# Power_Board.net
KiCad netlist of a schematic drawn in Altium Designer
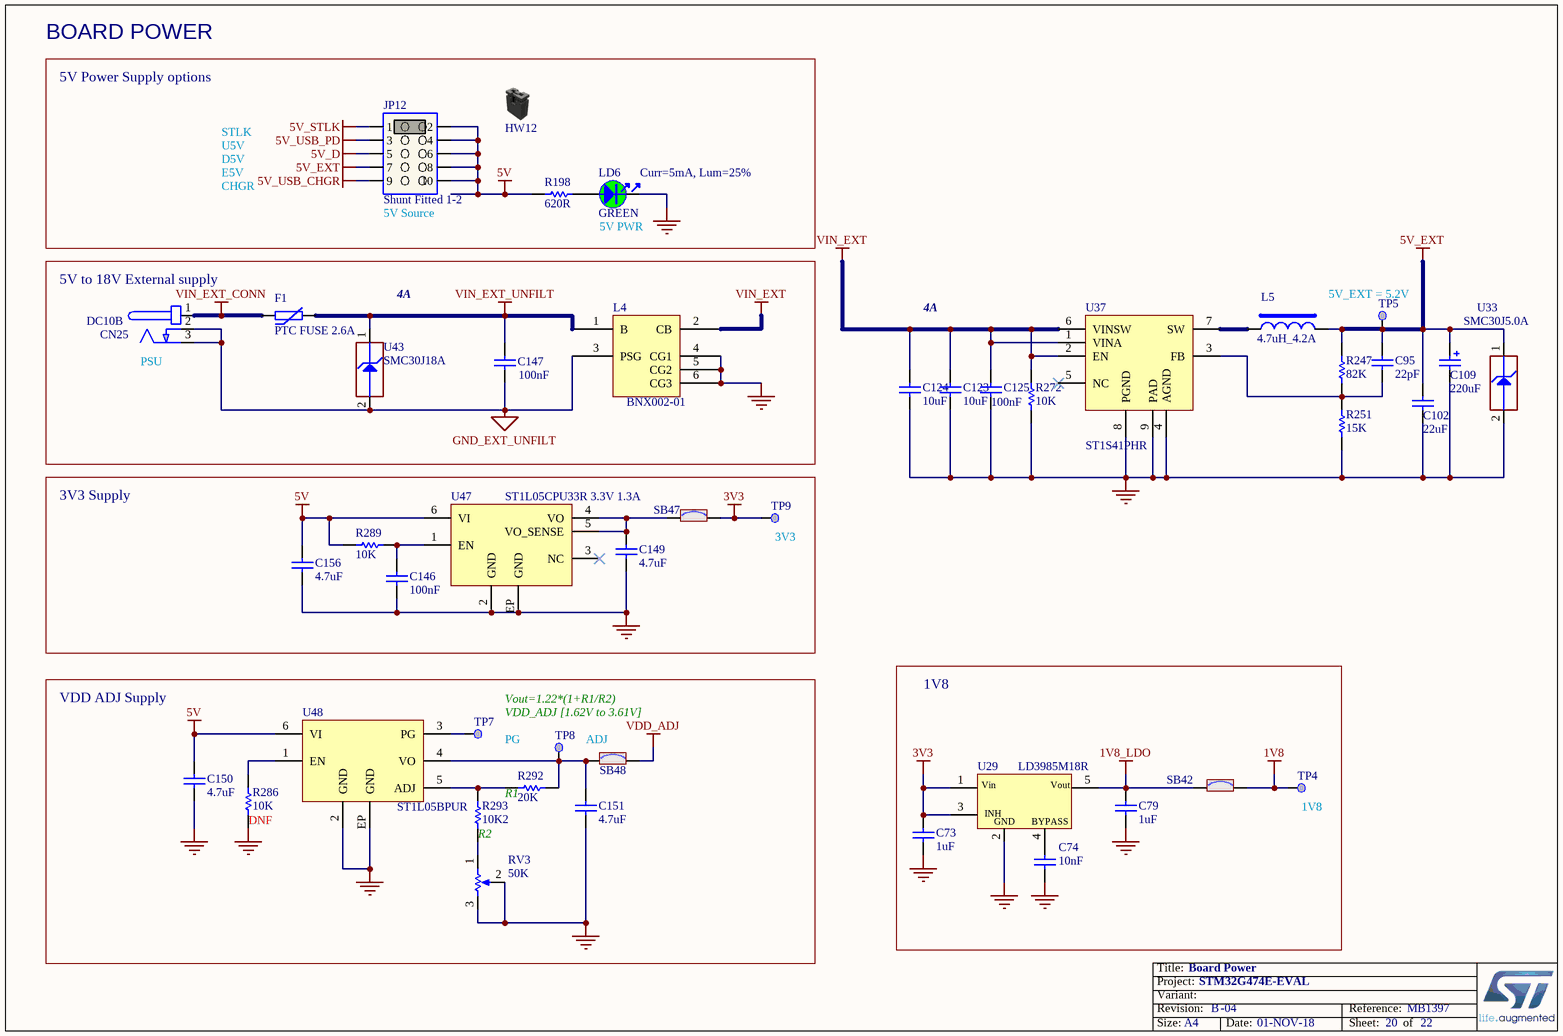
[diagram p0: Power_Board.SchDoc]

(export (version "E")
  (design (tool "Eeschema 10.0.6"))
  (components
    (comp (ref "C73")
      (value "1uF")
      (footprint "C0603")
      (description "Capacitor, MLCC, 1uF, 16V, X5R, 10%, 0603, T=0,8mm")
      (fields
        (field (name "INTERNAL_PART_NUMBER") "MCD-00010")
        (field (name "MANUFACTURER_PART_NUMBER") "CC0603KRX5R7BB105")
        (field (name "PROVIDED_BY") "SUBCO")
      )
      (libsource (lib "MCD_PARTS_database") (part "Capacitor"))
    )
    (comp (ref "C74")
      (value "10nF")
      (footprint "C0402")
      (description "Capacitor, MLCC, 10nF, 16V, X7R, 10%, 0402, T=0.5mm")
      (fields
        (field (name "INTERNAL_PART_NUMBER") "MCD-00011")
        (field (name "MANUFACTURER_PART_NUMBER") "CC0402KRX7R7BB103")
        (field (name "PROVIDED_BY") "SUBCO")
      )
      (libsource (lib "MCD_PARTS_database") (part "Capacitor"))
    )
    (comp (ref "C79")
      (value "1uF")
      (footprint "C0603")
      (description "Capacitor, MLCC, 1uF, 16V, X5R, 10%, 0603, T=0,8mm")
      (fields
        (field (name "INTERNAL_PART_NUMBER") "MCD-00010")
        (field (name "MANUFACTURER_PART_NUMBER") "CC0603KRX5R7BB105")
        (field (name "PROVIDED_BY") "SUBCO")
      )
      (libsource (lib "MCD_PARTS_database") (part "Capacitor"))
    )
    (comp (ref "C95")
      (value "22pF")
      (footprint "C0402")
      (description "Capacitor, MLCC, 22pF, 50V, C0G, 5%, 0402, T=0,5mm")
      (fields
        (field (name "INTERNAL_PART_NUMBER") "MCD-00203")
        (field (name "MANUFACTURER_PART_NUMBER") "GRM1555C1H220JA01")
        (field (name "PROVIDED_BY") "SUBCO")
      )
      (libsource (lib "MCD_PARTS_database") (part "Capacitor"))
    )
    (comp (ref "C102")
      (value "22uF")
      (footprint "C0805")
      (description "Capacitor, MLCC, 22uF, 6V3, X5R, 20%, 0805, T=1,25mm")
      (fields
        (field (name "INTERNAL_PART_NUMBER") "MCD-00101")
        (field (name "MANUFACTURER_PART_NUMBER") "GRM21BR60J226ME39L")
        (field (name "PROVIDED_BY") "SUBCO")
      )
      (libsource (lib "MCD_PARTS_database") (part "Capacitor"))
    )
    (comp (ref "C109")
      (value "220uF")
      (footprint "CPOL_TAJ-C_2312_H2P6")
      (description "Capacitor, Tantalum, 220uF, 10V, 10%, TypeC")
      (fields
        (field (name "INTERNAL_PART_NUMBER") "MCD-00142")
        (field (name "MANUFACTURER_PART_NUMBER") "TAJC227K010R")
        (field (name "PROVIDED_BY") "SUBCO")
      )
      (libsource (lib "MCD_PARTS_database") (part "Cap_POL_TANA"))
    )
    (comp (ref "C123")
      (value "10uF")
      (footprint "C1210")
      (description "Capacitor, X7R, 10µF, 50V, 20%, 1210, T=2.5mm")
      (fields
        (field (name "INTERNAL_PART_NUMBER") "MCD-01056")
        (field (name "MANUFACTURER_PART_NUMBER") "C3225X7R1H106M250AC")
        (field (name "PROVIDED_BY") "SUBCO")
      )
      (libsource (lib "MCD_PARTS_database") (part "Capacitor"))
    )
    (comp (ref "C124")
      (value "10uF")
      (footprint "C1210")
      (description "Capacitor, X7R, 10µF, 50V, 20%, 1210, T=2.5mm")
      (fields
        (field (name "INTERNAL_PART_NUMBER") "MCD-01056")
        (field (name "MANUFACTURER_PART_NUMBER") "C3225X7R1H106M250AC")
        (field (name "PROVIDED_BY") "SUBCO")
      )
      (libsource (lib "MCD_PARTS_database") (part "Capacitor"))
    )
    (comp (ref "C125")
      (value "100nF")
      (footprint "C0402")
      (description "Capacitor, MLCC, 100nF, 16V, X7R, 10%, 0402, T=0.5mm")
      (fields
        (field (name "INTERNAL_PART_NUMBER") "MCD-00006")
        (field (name "MANUFACTURER_PART_NUMBER") "CC0402KRX7R7BB104")
        (field (name "PROVIDED_BY") "SUBCO")
      )
      (libsource (lib "MCD_PARTS_database") (part "Capacitor"))
    )
    (comp (ref "C146")
      (value "100nF")
      (footprint "C0402")
      (description "Capacitor, MLCC, 100nF, 16V, X7R, 10%, 0402, T=0.5mm")
      (fields
        (field (name "INTERNAL_PART_NUMBER") "MCD-00006")
        (field (name "MANUFACTURER_PART_NUMBER") "CC0402KRX7R7BB104")
        (field (name "PROVIDED_BY") "SUBCO")
      )
      (libsource (lib "MCD_PARTS_database") (part "Capacitor"))
    )
    (comp (ref "C147")
      (value "100nF")
      (footprint "C0402")
      (description "Capacitor, MLCC, 100nF, 16V, X7R, 10%, 0402, T=0.5mm")
      (fields
        (field (name "INTERNAL_PART_NUMBER") "MCD-00006")
        (field (name "MANUFACTURER_PART_NUMBER") "CC0402KRX7R7BB104")
        (field (name "PROVIDED_BY") "SUBCO")
      )
      (libsource (lib "MCD_PARTS_database") (part "Capacitor"))
    )
    (comp (ref "C149")
      (value "4.7uF")
      (footprint "C0603")
      (description "Capacitor, MLCC, 4.7uF, 16V, X5R, 10%, 0603, T=0.8mm")
      (fields
        (field (name "INTERNAL_PART_NUMBER") "MCD-00009")
        (field (name "MANUFACTURER_PART_NUMBER") "CC0603KRX5R7BB475")
        (field (name "PROVIDED_BY") "SUBCO")
      )
      (libsource (lib "MCD_PARTS_database") (part "Capacitor"))
    )
    (comp (ref "C150")
      (value "4.7uF")
      (footprint "C0603")
      (description "Capacitor, MLCC, 4.7uF, 16V, X5R, 10%, 0603, T=0.8mm")
      (fields
        (field (name "INTERNAL_PART_NUMBER") "MCD-00009")
        (field (name "MANUFACTURER_PART_NUMBER") "CC0603KRX5R7BB475")
        (field (name "PROVIDED_BY") "SUBCO")
      )
      (libsource (lib "MCD_PARTS_database") (part "Capacitor"))
    )
    (comp (ref "C151")
      (value "4.7uF")
      (footprint "C0603")
      (description "Capacitor, MLCC, 4.7uF, 16V, X5R, 10%, 0603, T=0.8mm")
      (fields
        (field (name "INTERNAL_PART_NUMBER") "MCD-00009")
        (field (name "MANUFACTURER_PART_NUMBER") "CC0603KRX5R7BB475")
        (field (name "PROVIDED_BY") "SUBCO")
      )
      (libsource (lib "MCD_PARTS_database") (part "Capacitor"))
    )
    (comp (ref "C156")
      (value "4.7uF")
      (footprint "C0603")
      (description "Capacitor, MLCC, 4.7uF, 16V, X5R, 10%, 0603, T=0.8mm")
      (fields
        (field (name "INTERNAL_PART_NUMBER") "MCD-00009")
        (field (name "MANUFACTURER_PART_NUMBER") "CC0603KRX5R7BB475")
        (field (name "PROVIDED_BY") "SUBCO")
      )
      (libsource (lib "MCD_PARTS_database") (part "Capacitor"))
    )
    (comp (ref "CN25")
      (value "DC10B")
      (footprint "CON_DC-POWER-SOCKET_CLIFF_FC68149_DC10B")
      (description "DC-Power-Jack, 2.5mm, 5A, RA, TH")
      (fields
        (field (name "INTERNAL_PART_NUMBER") "MCD-00173")
        (field (name "MANUFACTURER") "CLIFF")
        (field (name "PROVIDED_BY") "SUBCO")
      )
      (libsource (lib "MCD_PARTS_database") (part "Power_Jack_DC10B"))
    )
    (comp (ref "F1")
      (value "PTC FUSE 2.6A")
      (footprint "PTC_BEL-FUSE_1812_0ZCG0260FF2C")
      (description "SMD, PTC resettable fuse, IH:2.6A, IT:5A, Vdc_max:8V, Rmax:47mohm, BELFUSE")
      (fields
        (field (name "INTERNAL_PART_NUMBER") "MCD-00624")
        (field (name "MANUFACTURER_PART_NUMBER") "0ZCG0260FF2C")
        (field (name "PROVIDED_BY") "SUBCO")
      )
      (libsource (lib "MCD_PARTS_database") (part "0ZCG0260FF2C"))
    )
    (comp (ref "HW12")
      (value "Shunt Black 2.54mm")
      (description "SHUNT 2.54mm BLACK")
      (fields
        (field (name "INTERNAL_PART_NUMBER") "MCD-00043")
        (field (name "MANUFACTURER_PART_NUMBER") "SNT-100-BK-G")
        (field (name "PROVIDED_BY") "SUBCO")
      )
      (libsource (lib "MCD_PARTS_database") (part "Shunt Black 2.54mm"))
    )
    (comp (ref "JP12")
      (value "Shunt Fitted 1-2")
      (footprint "CON_SAMTEC_TSW-105-07-X-D")
      (description "Header, 5x2, 2,54mm, VR, TH, Height 5.84mm/2.54mm - Shunt Fitted 1-2")
      (fields
        (field (name "INTERNAL_PART_NUMBER") "MCD-01203")
        (field (name "MANUFACTURER_PART_NUMBER") "TSW-105-07-x-D")
        (field (name "PROVIDED_BY") "SUBCO")
      )
      (libsource (lib "MCD_PARTS_database") (part "Jumper_Header 5x2 Fitted 1-2"))
    )
    (comp (ref "L4")
      (value "BNX002-01")
      (footprint "FIL_MURATA_BNX002-01")
      (description "Through HOLE DC power EMI line filter, 40dB min (1MHz - 1GHz) insertion loss")
      (fields
        (field (name "INTERNAL_PART_NUMBER") "MCD-00150")
        (field (name "MANUFACTURER") "MURATA")
        (field (name "PROVIDED_BY") "SUBCO")
      )
      (libsource (lib "MCD_PARTS_database") (part "BNX002-01"))
    )
    (comp (ref "L5")
      (value "4.7uH_4.2A")
      (footprint "IND_TDK_VLS6045EX-4R7M")
      (description "FIXED IND 4.7UH 4.2A 35 MOHM SMD")
      (fields
        (field (name "INTERNAL_PART_NUMBER") "MCD-01239")
        (field (name "MANUFACTURER_PART_NUMBER") "VLS6045EX-4R7M")
        (field (name "PROVIDED_BY") "SUBCO")
      )
      (libsource (lib "MCD_PARTS_database") (part "INDUCTOR_POWER"))
    )
    (comp (ref "LD6")
      (value "GREEN")
      (footprint "LED_0603_OSRAM_LG-Q396-PS-35_GREEN_1A2K_H0P4")
      (description "LED Green, 0603 SMD, Forward Voltage Typ=2V, Max=2.5V")
      (fields
        (field (name "INTERNAL_PART_NUMBER") "MCD-00588")
        (field (name "MANUFACTURER_PART_NUMBER") "LG Q396-PS-35")
        (field (name "PROVIDED_BY") "SUBCO")
      )
      (libsource (lib "MCD_PARTS_database") (part "LED_green"))
    )
    (comp (ref "R198")
      (value "620R")
      (footprint "R0603")
      (description "Resistor,620R,0603,1%,1/10W")
      (fields
        (field (name "INTERNAL_PART_NUMBER") "MCD-00500")
        (field (name "MANUFACTURER_PART_NUMBER") "RC0603FR-07620RL")
        (field (name "PROVIDED_BY") "SUBCO")
      )
      (libsource (lib "MCD_PARTS_database") (part "Resistor"))
    )
    (comp (ref "R247")
      (value "82K")
      (footprint "R0402")
      (description "Resistor,82K,0402,1%,1/16W")
      (fields
        (field (name "INTERNAL_PART_NUMBER") "MCD-00531")
        (field (name "MANUFACTURER_PART_NUMBER") "RC0402FR-0782KL")
        (field (name "PROVIDED_BY") "SUBCO")
      )
      (libsource (lib "MCD_PARTS_database") (part "Resistor"))
    )
    (comp (ref "R251")
      (value "15K")
      (footprint "R0402")
      (description "Resistor,15K,0402,5%,1/16W")
      (fields
        (field (name "INTERNAL_PART_NUMBER") "MCD-00285")
        (field (name "MANUFACTURER_PART_NUMBER") "RC0402JR-0715KL")
        (field (name "PROVIDED_BY") "SUBCO")
      )
      (libsource (lib "MCD_PARTS_database") (part "Resistor"))
    )
    (comp (ref "R272")
      (value "10K")
      (footprint "R0402")
      (description "Resistor,10K,0402,1%,1/16W")
      (fields
        (field (name "INTERNAL_PART_NUMBER") "MCD-00053")
        (field (name "MANUFACTURER_PART_NUMBER") "RC0402FR-0710KL")
        (field (name "PROVIDED_BY") "SUBCO")
      )
      (libsource (lib "MCD_PARTS_database") (part "Resistor"))
    )
    (comp (ref "R286")
      (value "10K")
      (footprint "R0402")
      (description "Resistor,10K,0402,1%,1/16W")
      (fields
        (field (name "INTERNAL_PART_NUMBER") "MCD-00053")
        (field (name "MANUFACTURER_PART_NUMBER") "RC0402FR-0710KL")
        (field (name "PROVIDED_BY") "SUBCO")
      )
      (libsource (lib "MCD_PARTS_database") (part "Resistor"))
    )
    (comp (ref "R289")
      (value "10K")
      (footprint "R0402")
      (description "Resistor,10K,0402,1%,1/16W")
      (fields
        (field (name "INTERNAL_PART_NUMBER") "MCD-00053")
        (field (name "MANUFACTURER_PART_NUMBER") "RC0402FR-0710KL")
        (field (name "PROVIDED_BY") "SUBCO")
      )
      (libsource (lib "MCD_PARTS_database") (part "Resistor"))
    )
    (comp (ref "R292")
      (value "20K")
      (footprint "R0603")
      (description "Resistor,20K,0603,1%,1/10W")
      (fields
        (field (name "INTERNAL_PART_NUMBER") "MCD-00422")
        (field (name "MANUFACTURER_PART_NUMBER") "RC0603FR-0720KL")
        (field (name "PROVIDED_BY") "SUBCO")
      )
      (libsource (lib "MCD_PARTS_database") (part "Resistor"))
    )
    (comp (ref "R293")
      (value "10K2")
      (footprint "R0603")
      (description "Resistor,10K2,0603,1%,1/10W")
      (fields
        (field (name "INTERNAL_PART_NUMBER") "MCD-01155")
        (field (name "MANUFACTURER_PART_NUMBER") "RC0603FR-0710K2L")
        (field (name "PROVIDED_BY") "SUBCO")
      )
      (libsource (lib "MCD_PARTS_database") (part "Resistor"))
    )
    (comp (ref "RV3")
      (value "50K")
      (footprint "POT_BOURNS_3386P")
      (description "TRIMMER 50K OHM 0.5W PC PIN")
      (fields
        (field (name "INTERNAL_PART_NUMBER") "MCD-01156")
        (field (name "MANUFACTURER_PART_NUMBER") "3386P-1-503")
        (field (name "PROVIDED_BY") "SUBCO")
      )
      (libsource (lib "MCD_PARTS_database") (part "POTENTIOMETER"))
    )
    (comp (ref "SB42")
      (value "SB_ON")
      (footprint "SOLDER-BRIDGE_R0603-0R")
      (description "Solder Bridge ON")
      (fields
        (field (name "INTERNAL_PART_NUMBER") "MCD-00071")
        (field (name "MANUFACTURER_PART_NUMBER") "RC0603JR-070RL")
        (field (name "PROVIDED_BY") "SUBCO")
      )
      (libsource (lib "MCD_PARTS_database") (part "SB_ON"))
    )
    (comp (ref "SB47")
      (value "SB_ON")
      (footprint "SOLDER-BRIDGE_R0603-0R")
      (description "Solder Bridge ON")
      (fields
        (field (name "INTERNAL_PART_NUMBER") "MCD-00071")
        (field (name "MANUFACTURER_PART_NUMBER") "RC0603JR-070RL")
        (field (name "PROVIDED_BY") "SUBCO")
      )
      (libsource (lib "MCD_PARTS_database") (part "SB_ON"))
    )
    (comp (ref "SB48")
      (value "SB_ON")
      (footprint "SOLDER-BRIDGE_R0603-0R")
      (description "Solder Bridge ON")
      (fields
        (field (name "INTERNAL_PART_NUMBER") "MCD-00071")
        (field (name "MANUFACTURER_PART_NUMBER") "RC0603JR-070RL")
        (field (name "PROVIDED_BY") "SUBCO")
      )
      (libsource (lib "MCD_PARTS_database") (part "SB_ON"))
    )
    (comp (ref "TP4")
      (value "Test Point")
      (footprint "TP_SMD_1MM")
      (description "Test Point 1mm")
      (fields (field (name "INTERNAL_PART_NUMBER") "MCD-00074") (field (name "MANUFACTURER") "n/a"))
      (libsource (lib "MCD_PARTS_database") (part "Test Point"))
    )
    (comp (ref "TP5")
      (value "Test Point")
      (footprint "TP_SMD_1MM")
      (description "Test Point 1mm")
      (fields (field (name "INTERNAL_PART_NUMBER") "MCD-00074") (field (name "MANUFACTURER") "n/a"))
      (libsource (lib "") (part "Test Point_1"))
    )
    (comp (ref "TP7")
      (value "Test Point")
      (footprint "TP_SMD_1MM")
      (description "Test Point 1mm")
      (fields (field (name "INTERNAL_PART_NUMBER") "MCD-00074") (field (name "MANUFACTURER") "n/a"))
      (libsource (lib "MCD_PARTS_database") (part "Test Point"))
    )
    (comp (ref "TP8")
      (value "Test Point")
      (footprint "TP_SMD_1MM")
      (description "Test Point 1mm")
      (fields (field (name "INTERNAL_PART_NUMBER") "MCD-00074") (field (name "MANUFACTURER") "n/a"))
      (libsource (lib "") (part "Test Point_1"))
    )
    (comp (ref "TP9")
      (value "Test Point")
      (footprint "TP_SMD_1MM")
      (description "Test Point 1mm")
      (fields (field (name "INTERNAL_PART_NUMBER") "MCD-00074") (field (name "MANUFACTURER") "n/a"))
      (libsource (lib "MCD_PARTS_database") (part "Test Point"))
    )
    (comp (ref "U29")
      (value "LD3985M18R")
      (footprint "REG_SOT23-5L")
      (description "Ultra low drop-low noise BiCMOS voltage, regulators low ESR capacitors compatible")
      (fields
        (field (name "INTERNAL_PART_NUMBER") "MCD-00078")
        (field (name "MANUFACTURER") "STMICROELECTRONICS")
        (field (name "PROVIDED_BY") "SUBCO with ST control")
      )
      (libsource (lib "MCD_PARTS_database") (part "LD3985M18R"))
    )
    (comp (ref "U33")
      (value "SMC30J5.0A")
      (footprint "DIO_SMC_DO214-AB_1K_2A")
      (description "3000 W Transil")
      (fields
        (field (name "INTERNAL_PART_NUMBER") "MCD-01231")
        (field (name "MANUFACTURER") "STMICROELECTRONICS")
        (field (name "PROVIDED_BY") "SUBCO with ST control")
      )
      (libsource (lib "MCD_PARTS_database") (part "ESD-TRANSIL"))
    )
    (comp (ref "U37")
      (value "ST1S41PHR")
      (footprint "ICC_HSOP8-EPAD_3P90X4P90_P127")
      (description "4A step-down switching regulator")
      (fields
        (field (name "INTERNAL_PART_NUMBER") "MCD-01237")
        (field (name "MANUFACTURER") "STMICROELECTRONICS")
        (field (name "PROVIDED_BY") "SUBCO with ST control")
      )
      (libsource (lib "MCD_PARTS_database") (part "ST1S41"))
    )
    (comp (ref "U43")
      (value "SMC30J18A")
      (footprint "DIO_SMC_DO214-AB_1K_2A")
      (description "3000 W Transil")
      (fields
        (field (name "INTERNAL_PART_NUMBER") "MCD-01238")
        (field (name "MANUFACTURER") "STMICROELECTRONICS")
        (field (name "PROVIDED_BY") "SUBCO with ST control")
      )
      (libsource (lib "MCD_PARTS_database") (part "ESD-TRANSIL"))
    )
    (comp (ref "U47")
      (value "ST1L05CPU33R 3.3V 1.3A")
      (footprint "ICC_DFN6-EPAD_3X3_P095")
      (description "LDO, 3.3V, 1.3A, Very low quiescent current BiCMOS voltage regulator")
      (fields
        (field (name "INTERNAL_PART_NUMBER") "MCD-01025")
        (field (name "MANUFACTURER_PART_NUMBER") "ST1L05CPU33R")
        (field (name "PROVIDED_BY") "SUBCO with ST control")
      )
      (libsource (lib "MCD_PARTS_database") (part "ST1L05CPU33R"))
    )
    (comp (ref "U48")
      (value "ST1L05BPUR")
      (footprint "ICC_DFN6-EPAD_3X3_P095")
      (description "LDO Linear Voltage Regulator IC Positive Adjustable 1 Output Adjustable 1.3A 6-DFN (3x3)")
      (fields
        (field (name "INTERNAL_PART_NUMBER") "MCD-00581")
        (field (name "MANUFACTURER") "STMICROELECTRONICS")
        (field (name "PROVIDED_BY") "SUBCO with ST control")
      )
      (libsource (lib "MCD_PARTS_database") (part "ST1L05BPUR"))
    )
  )
  (nets
    (net (code "1") (name "1V8") (class "Default")
      (node (ref "SB42") (pin "2") (pinfunction "2_2") (pintype "passive"))
      (node (ref "TP4") (pin "1") (pinfunction "1_1") (pintype "passive"))
    )
    (net (code "2") (name "1V8_LDO") (class "Default")
      (node (ref "C79") (pin "2") (pinfunction "2_2") (pintype "passive"))
      (node (ref "SB42") (pin "1") (pinfunction "1_1") (pintype "passive"))
      (node (ref "U29") (pin "5") (pinfunction "Vout_5") (pintype "passive"))
    )
    (net (code "3") (name "3V3") (class "Default")
      (node (ref "C73") (pin "2") (pinfunction "2_2") (pintype "passive"))
      (node (ref "SB47") (pin "2") (pinfunction "2_2") (pintype "passive"))
      (node (ref "TP9") (pin "1") (pinfunction "1_1") (pintype "passive"))
      (node (ref "U29") (pin "1") (pinfunction "Vin_1") (pintype "passive"))
      (node (ref "U29") (pin "3") (pinfunction "CE_3") (pintype "passive"))
    )
    (net (code "4") (name "5V") (class "Default")
      (node (ref "C150") (pin "1") (pinfunction "1_1") (pintype "passive"))
      (node (ref "C156") (pin "2") (pinfunction "2_2") (pintype "passive"))
      (node (ref "JP12") (pin "10") (pinfunction "10_10") (pintype "passive"))
      (node (ref "JP12") (pin "2") (pinfunction "2_2") (pintype "passive"))
      (node (ref "JP12") (pin "4") (pinfunction "4_4") (pintype "passive"))
      (node (ref "JP12") (pin "6") (pinfunction "6_6") (pintype "passive"))
      (node (ref "JP12") (pin "8") (pinfunction "8_8") (pintype "passive"))
      (node (ref "R198") (pin "1") (pinfunction "1_1") (pintype "passive"))
      (node (ref "R289") (pin "2") (pinfunction "2_2") (pintype "passive"))
      (node (ref "U47") (pin "6") (pinfunction "VI_6") (pintype "passive"))
      (node (ref "U48") (pin "6") (pinfunction "VI_6") (pintype "passive"))
    )
    (net (code "5") (name "5V_D") (class "Default")
      (node (ref "JP12") (pin "5") (pinfunction "5_5") (pintype "passive"))
    )
    (net (code "6") (name "5V_EXT") (class "Default")
      (node (ref "C102") (pin "2") (pinfunction "2_2") (pintype "passive"))
      (node (ref "C109") (pin "1") (pinfunction "1_1") (pintype "passive"))
      (node (ref "C95") (pin "2") (pinfunction "2_2") (pintype "passive"))
      (node (ref "JP12") (pin "7") (pinfunction "7_7") (pintype "passive"))
      (node (ref "L5") (pin "2") (pinfunction "2_2") (pintype "passive"))
      (node (ref "R247") (pin "2") (pinfunction "2_2") (pintype "passive"))
      (node (ref "TP5") (pin "1") (pinfunction "1_1") (pintype "passive"))
      (node (ref "U33") (pin "1") (pinfunction "IO1_1") (pintype "passive"))
    )
    (net (code "7") (name "5V_STLK") (class "Default")
      (node (ref "JP12") (pin "1") (pinfunction "1_1") (pintype "passive"))
    )
    (net (code "8") (name "5V_USB_CHGR") (class "Default")
      (node (ref "JP12") (pin "9") (pinfunction "9_9") (pintype "passive"))
    )
    (net (code "9") (name "5V_USB_PD") (class "Default")
      (node (ref "JP12") (pin "3") (pinfunction "3_3") (pintype "passive"))
    )
    (net (code "10") (name "GND") (class "Default")
      (node (ref "C102") (pin "1") (pinfunction "1_1") (pintype "passive"))
      (node (ref "C109") (pin "2") (pinfunction "2_2") (pintype "passive"))
      (node (ref "C123") (pin "1") (pinfunction "1_1") (pintype "passive"))
      (node (ref "C124") (pin "1") (pinfunction "1_1") (pintype "passive"))
      (node (ref "C125") (pin "1") (pinfunction "1_1") (pintype "passive"))
      (node (ref "C146") (pin "2") (pinfunction "2_2") (pintype "passive"))
      (node (ref "C149") (pin "1") (pinfunction "1_1") (pintype "passive"))
      (node (ref "C150") (pin "2") (pinfunction "2_2") (pintype "passive"))
      (node (ref "C151") (pin "1") (pinfunction "1_1") (pintype "passive"))
      (node (ref "C156") (pin "1") (pinfunction "1_1") (pintype "passive"))
      (node (ref "C73") (pin "1") (pinfunction "1_1") (pintype "passive"))
      (node (ref "C74") (pin "1") (pinfunction "1_1") (pintype "passive"))
      (node (ref "C79") (pin "1") (pinfunction "1_1") (pintype "passive"))
      (node (ref "L4") (pin "4") (pinfunction "CG1_4") (pintype "passive"))
      (node (ref "L4") (pin "5") (pinfunction "CG2_5") (pintype "passive"))
      (node (ref "L4") (pin "6") (pinfunction "CG3_6") (pintype "passive"))
      (node (ref "LD6") (pin "2") (pintype "passive"))
      (node (ref "R251") (pin "1") (pinfunction "1_1") (pintype "passive"))
      (node (ref "R272") (pin "1") (pinfunction "1_1") (pintype "passive"))
      (node (ref "R286") (pin "2") (pinfunction "2_2") (pintype "passive"))
      (node (ref "RV3") (pin "2") (pinfunction "TAP_2") (pintype "passive"))
      (node (ref "RV3") (pin "3") (pinfunction "TOP_3") (pintype "passive"))
      (node (ref "U29") (pin "2") (pinfunction "GND_2") (pintype "passive"))
      (node (ref "U33") (pin "2") (pinfunction "GND_2") (pintype "passive"))
      (node (ref "U37") (pin "4") (pinfunction "AGND_4") (pintype "passive"))
      (node (ref "U37") (pin "8") (pinfunction "PGND_8") (pintype "passive"))
      (node (ref "U37") (pin "9") (pinfunction "PAD_9") (pintype "passive"))
      (node (ref "U47") (pin "2") (pinfunction "GND_2") (pintype "passive"))
      (node (ref "U47") (pin "EP") (pinfunction "GND_EP") (pintype "passive"))
      (node (ref "U48") (pin "2") (pinfunction "GND_2") (pintype "passive"))
      (node (ref "U48") (pin "EP") (pinfunction "GND_EP") (pintype "passive"))
    )
    (net (code "11") (name "GND_EXT_UNFILT") (class "Default")
      (node (ref "C147") (pin "2") (pinfunction "2_2") (pintype "passive"))
      (node (ref "CN25") (pin "2") (pintype "passive"))
      (node (ref "CN25") (pin "3") (pintype "passive"))
      (node (ref "L4") (pin "3") (pinfunction "PSG_3") (pintype "passive"))
      (node (ref "U43") (pin "2") (pinfunction "GND_2") (pintype "passive"))
    )
    (net (code "12") (name "Net-(LD6-Pad1)") (class "Default")
      (node (ref "LD6") (pin "1") (pintype "passive"))
      (node (ref "R198") (pin "2") (pinfunction "2_2") (pintype "passive"))
    )
    (net (code "13") (name "Net-(RV3-BOT)") (class "Default")
      (node (ref "R293") (pin "1") (pinfunction "1_1") (pintype "passive"))
      (node (ref "RV3") (pin "1") (pinfunction "BOT_1") (pintype "passive"))
    )
    (net (code "14") (name "Net-(U29-BYPASS)") (class "Default")
      (node (ref "C74") (pin "2") (pinfunction "2_2") (pintype "passive"))
      (node (ref "U29") (pin "4") (pinfunction "BYPASS_4") (pintype "passive"))
    )
    (net (code "15") (name "Net-(U37-FB)") (class "Default")
      (node (ref "C95") (pin "1") (pinfunction "1_1") (pintype "passive"))
      (node (ref "R247") (pin "1") (pinfunction "1_1") (pintype "passive"))
      (node (ref "R251") (pin "2") (pinfunction "2_2") (pintype "passive"))
      (node (ref "U37") (pin "3") (pinfunction "FB_3") (pintype "passive"))
    )
    (net (code "16") (name "Net-(U37-SW)") (class "Default")
      (node (ref "L5") (pin "1") (pinfunction "1_1") (pintype "passive"))
      (node (ref "U37") (pin "7") (pinfunction "SW_7") (pintype "passive"))
    )
    (net (code "17") (name "Net-(U47-EN)") (class "Default")
      (node (ref "C146") (pin "1") (pinfunction "1_1") (pintype "passive"))
      (node (ref "R289") (pin "1") (pinfunction "1_1") (pintype "passive"))
      (node (ref "U47") (pin "1") (pinfunction "EN_1") (pintype "passive"))
    )
    (net (code "18") (name "Net-(U47-VO)") (class "Default")
      (node (ref "C149") (pin "2") (pinfunction "2_2") (pintype "passive"))
      (node (ref "SB47") (pin "1") (pinfunction "1_1") (pintype "passive"))
      (node (ref "U47") (pin "4") (pinfunction "VO_4") (pintype "passive"))
      (node (ref "U47") (pin "5") (pinfunction "VO_SENSE_5") (pintype "passive"))
    )
    (net (code "19") (name "Net-(U48-ADJ)") (class "Default")
      (node (ref "R292") (pin "1") (pinfunction "1_1") (pintype "passive"))
      (node (ref "R293") (pin "2") (pinfunction "2_2") (pintype "passive"))
      (node (ref "U48") (pin "5") (pinfunction "ADJ_5") (pintype "passive"))
    )
    (net (code "20") (name "Net-(U48-EN)") (class "Default")
      (node (ref "R286") (pin "1") (pinfunction "1_1") (pintype "passive"))
      (node (ref "U48") (pin "1") (pinfunction "EN_1") (pintype "passive"))
    )
    (net (code "21") (name "Net-(U48-PG)") (class "Default")
      (node (ref "TP7") (pin "1") (pinfunction "1_1") (pintype "passive"))
      (node (ref "U48") (pin "3") (pinfunction "PG_3") (pintype "passive"))
    )
    (net (code "22") (name "Net-(U48-VO)") (class "Default")
      (node (ref "C151") (pin "2") (pinfunction "2_2") (pintype "passive"))
      (node (ref "R292") (pin "2") (pinfunction "2_2") (pintype "passive"))
      (node (ref "SB48") (pin "1") (pinfunction "1_1") (pintype "passive"))
      (node (ref "TP8") (pin "1") (pinfunction "1_1") (pintype "passive"))
      (node (ref "U48") (pin "4") (pinfunction "VO_4") (pintype "passive"))
    )
    (net (code "23") (name "VDD_ADJ") (class "Default")
      (node (ref "SB48") (pin "2") (pinfunction "2_2") (pintype "passive"))
    )
    (net (code "24") (name "VIN_EXT") (class "Default")
      (node (ref "C123") (pin "2") (pinfunction "2_2") (pintype "passive"))
      (node (ref "C124") (pin "2") (pinfunction "2_2") (pintype "passive"))
      (node (ref "C125") (pin "2") (pinfunction "2_2") (pintype "passive"))
      (node (ref "L4") (pin "2") (pinfunction "CB_2") (pintype "passive"))
      (node (ref "R272") (pin "2") (pinfunction "2_2") (pintype "passive"))
      (node (ref "U37") (pin "1") (pinfunction "VINA_1") (pintype "passive"))
      (node (ref "U37") (pin "2") (pinfunction "EN_2") (pintype "passive"))
      (node (ref "U37") (pin "6") (pinfunction "VINSW_6") (pintype "passive"))
    )
    (net (code "25") (name "VIN_EXT_CONN") (class "Default")
      (node (ref "CN25") (pin "1") (pintype "passive"))
      (node (ref "F1") (pin "1") (pinfunction "1_1") (pintype "passive"))
    )
    (net (code "26") (name "VIN_EXT_UNFILT") (class "Default")
      (node (ref "C147") (pin "1") (pinfunction "1_1") (pintype "passive"))
      (node (ref "F1") (pin "2") (pinfunction "2_2") (pintype "passive"))
      (node (ref "L4") (pin "1") (pinfunction "B_1") (pintype "passive"))
      (node (ref "U43") (pin "1") (pinfunction "IO1_1") (pintype "passive"))
    )
    (net (code "27") (name "unconnected-(U37-NC-Pad5)") (class "Default")
      (node (ref "U37") (pin "5") (pinfunction "NC_5") (pintype "passive+no_connect"))
    )
    (net (code "28") (name "unconnected-(U47-NC-Pad3)") (class "Default")
      (node (ref "U47") (pin "3") (pinfunction "NC_3") (pintype "passive+no_connect"))
    )
  )
)
